# Pi-Switch-schematics.net
KiCad netlist of a schematic drawn in EAGLE
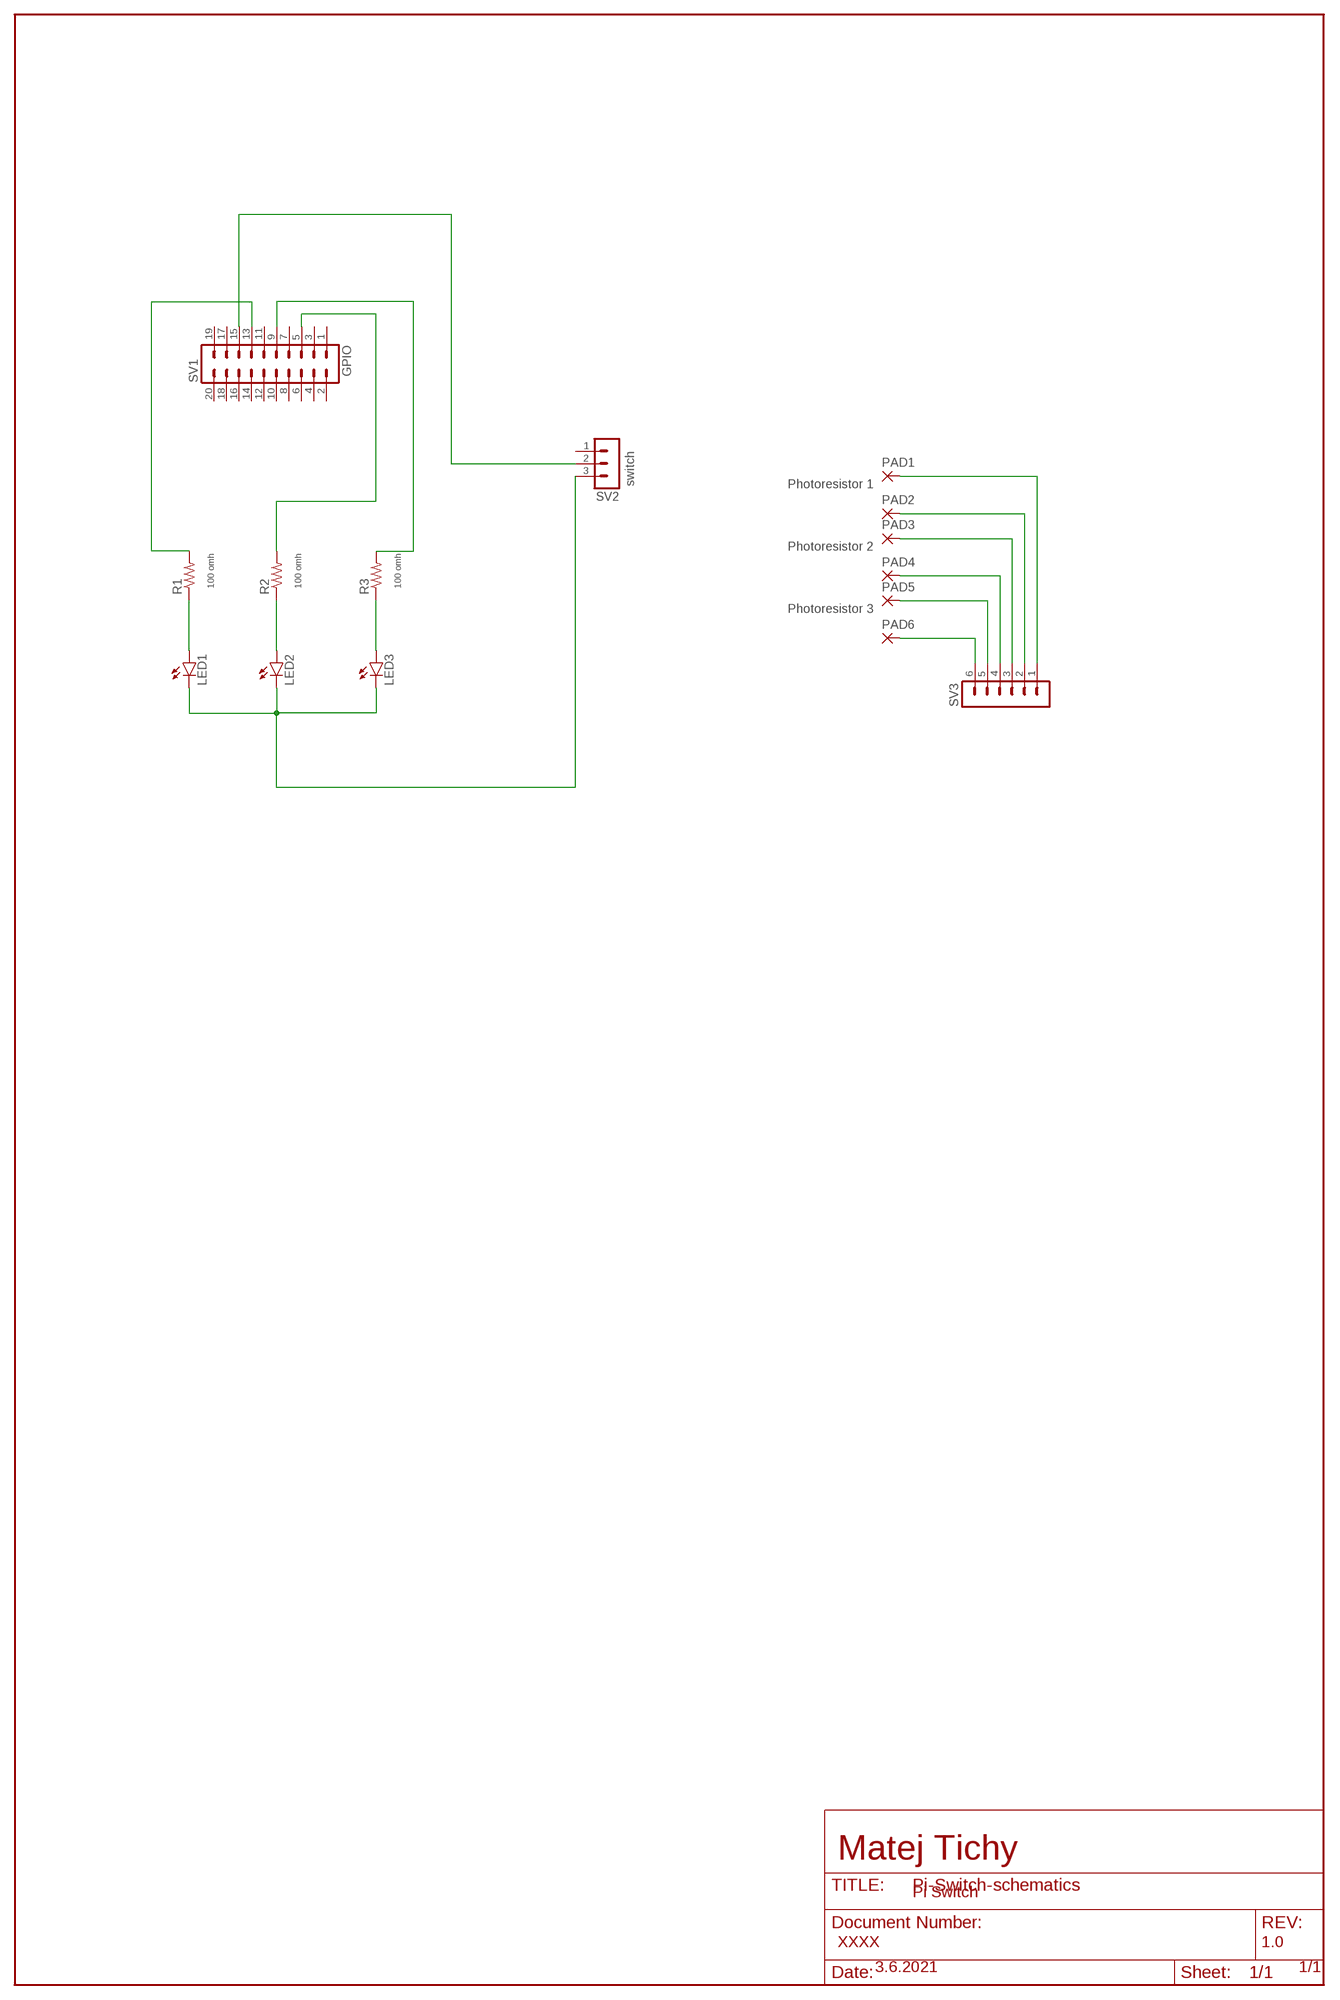
[diagram p0: schematic, sheet 1]

(export (version "E")
  (design (tool "Eeschema 10.0.6"))
  (components
    (comp (ref "LED1")
      (value "LED5MM")
      (footprint "eagle-import:LED5MM")
      (libsource (lib "eagle-import") (part "LED5MM"))
    )
    (comp (ref "LED2")
      (value "LED5MM")
      (footprint "eagle-import:LED5MM")
      (libsource (lib "eagle-import") (part "LED5MM"))
    )
    (comp (ref "LED3")
      (value "LED5MM")
      (footprint "eagle-import:LED5MM")
      (libsource (lib "eagle-import") (part "LED5MM"))
    )
    (comp (ref "PAD1")
      (value "1,6/0,8")
      (footprint "eagle-import:1,6_0,8")
      (libsource (lib "eagle-import") (part "1,6/0,8"))
    )
    (comp (ref "PAD2")
      (value "1,6/0,8")
      (footprint "eagle-import:1,6_0,8")
      (libsource (lib "eagle-import") (part "1,6/0,8"))
    )
    (comp (ref "PAD3")
      (value "1,6/0,8")
      (footprint "eagle-import:1,6_0,8")
      (libsource (lib "eagle-import") (part "1,6/0,8"))
    )
    (comp (ref "PAD4")
      (value "1,6/0,8")
      (footprint "eagle-import:1,6_0,8")
      (libsource (lib "eagle-import") (part "1,6/0,8"))
    )
    (comp (ref "PAD5")
      (value "1,6/0,8")
      (footprint "eagle-import:1,6_0,8")
      (libsource (lib "eagle-import") (part "1,6/0,8"))
    )
    (comp (ref "PAD6")
      (value "1,6/0,8")
      (footprint "eagle-import:1,6_0,8")
      (libsource (lib "eagle-import") (part "1,6/0,8"))
    )
    (comp (ref "R1")
      (value "R-US_0204/7")
      (footprint "eagle-import:0204_7")
      (libsource (lib "eagle-import") (part "R-US_0204/7"))
    )
    (comp (ref "R2")
      (value "R-US_0204/7")
      (footprint "eagle-import:0204_7")
      (libsource (lib "eagle-import") (part "R-US_0204/7"))
    )
    (comp (ref "R3")
      (value "R-US_0204/7")
      (footprint "eagle-import:0204_7")
      (libsource (lib "eagle-import") (part "R-US_0204/7"))
    )
    (comp (ref "SV1")
      (value "MA10-2")
      (footprint "eagle-import:MA10-2")
      (libsource (lib "eagle-import") (part "MA10-2"))
    )
    (comp (ref "SV2")
      (value "MA03-1")
      (footprint "eagle-import:MA03-1")
      (libsource (lib "eagle-import") (part "MA03-1"))
    )
    (comp (ref "SV3")
      (value "MA06-1")
      (footprint "eagle-import:MA06-1")
      (libsource (lib "eagle-import") (part "MA06-1"))
    )
  )
  (nets
    (net (code "1") (name "Net-(LED1-C)") (class "Default")
      (node (ref "LED1") (pin "K") (pinfunction "C_K") (pintype "passive"))
      (node (ref "LED2") (pin "K") (pinfunction "C_K") (pintype "passive"))
      (node (ref "LED3") (pin "K") (pinfunction "C_K") (pintype "passive"))
      (node (ref "SV2") (pin "3") (pinfunction "3_3") (pintype "passive"))
    )
    (net (code "2") (name "Net-(LED1-PadA)") (class "Default")
      (node (ref "LED1") (pin "A") (pinfunction "A_A") (pintype "passive"))
      (node (ref "R1") (pin "1") (pinfunction "1_1") (pintype "passive"))
    )
    (net (code "3") (name "Net-(LED2-PadA)") (class "Default")
      (node (ref "LED2") (pin "A") (pinfunction "A_A") (pintype "passive"))
      (node (ref "R2") (pin "1") (pinfunction "1_1") (pintype "passive"))
    )
    (net (code "4") (name "Net-(LED3-PadA)") (class "Default")
      (node (ref "LED3") (pin "A") (pinfunction "A_A") (pintype "passive"))
      (node (ref "R3") (pin "1") (pinfunction "1_1") (pintype "passive"))
    )
    (net (code "5") (name "Net-(PAD1-P)") (class "Default")
      (node (ref "PAD1") (pin "1") (pinfunction "P_1") (pintype "passive"))
      (node (ref "SV3") (pin "1") (pinfunction "1_1") (pintype "passive"))
    )
    (net (code "6") (name "Net-(PAD2-P)") (class "Default")
      (node (ref "PAD2") (pin "1") (pinfunction "P_1") (pintype "passive"))
      (node (ref "SV3") (pin "2") (pinfunction "2_2") (pintype "passive"))
    )
    (net (code "7") (name "Net-(PAD3-P)") (class "Default")
      (node (ref "PAD3") (pin "1") (pinfunction "P_1") (pintype "passive"))
      (node (ref "SV3") (pin "3") (pinfunction "3_3") (pintype "passive"))
    )
    (net (code "8") (name "Net-(PAD4-P)") (class "Default")
      (node (ref "PAD4") (pin "1") (pinfunction "P_1") (pintype "passive"))
      (node (ref "SV3") (pin "4") (pinfunction "4_4") (pintype "passive"))
    )
    (net (code "9") (name "Net-(PAD5-P)") (class "Default")
      (node (ref "PAD5") (pin "1") (pinfunction "P_1") (pintype "passive"))
      (node (ref "SV3") (pin "5") (pinfunction "5_5") (pintype "passive"))
    )
    (net (code "10") (name "Net-(PAD6-P)") (class "Default")
      (node (ref "PAD6") (pin "1") (pinfunction "P_1") (pintype "passive"))
      (node (ref "SV3") (pin "6") (pinfunction "6_6") (pintype "passive"))
    )
    (net (code "11") (name "Net-(R1-Pad2)") (class "Default")
      (node (ref "R1") (pin "2") (pinfunction "2_2") (pintype "passive"))
      (node (ref "SV1") (pin "13") (pinfunction "13_13") (pintype "passive"))
    )
    (net (code "12") (name "Net-(R2-Pad2)") (class "Default")
      (node (ref "R2") (pin "2") (pinfunction "2_2") (pintype "passive"))
      (node (ref "SV1") (pin "5") (pinfunction "5_5") (pintype "passive"))
    )
    (net (code "13") (name "Net-(R3-Pad2)") (class "Default")
      (node (ref "R3") (pin "2") (pinfunction "2_2") (pintype "passive"))
      (node (ref "SV1") (pin "9") (pinfunction "9_9") (pintype "passive"))
    )
    (net (code "14") (name "Net-(SV1-Pad15)") (class "Default")
      (node (ref "SV1") (pin "15") (pinfunction "15_15") (pintype "passive"))
      (node (ref "SV2") (pin "2") (pinfunction "2_2") (pintype "passive"))
    )
    (net (code "15") (name "unconnected-(SV1-Pad1)") (class "Default")
      (node (ref "SV1") (pin "1") (pinfunction "1_1") (pintype "passive"))
    )
    (net (code "16") (name "unconnected-(SV1-Pad2)") (class "Default")
      (node (ref "SV1") (pin "2") (pinfunction "2_2") (pintype "passive"))
    )
    (net (code "17") (name "unconnected-(SV1-Pad3)") (class "Default")
      (node (ref "SV1") (pin "3") (pinfunction "3_3") (pintype "passive"))
    )
    (net (code "18") (name "unconnected-(SV1-Pad4)") (class "Default")
      (node (ref "SV1") (pin "4") (pinfunction "4_4") (pintype "passive"))
    )
    (net (code "19") (name "unconnected-(SV1-Pad6)") (class "Default")
      (node (ref "SV1") (pin "6") (pinfunction "6_6") (pintype "passive"))
    )
    (net (code "20") (name "unconnected-(SV1-Pad7)") (class "Default")
      (node (ref "SV1") (pin "7") (pinfunction "7_7") (pintype "passive"))
    )
    (net (code "21") (name "unconnected-(SV1-Pad8)") (class "Default")
      (node (ref "SV1") (pin "8") (pinfunction "8_8") (pintype "passive"))
    )
    (net (code "22") (name "unconnected-(SV1-Pad10)") (class "Default")
      (node (ref "SV1") (pin "10") (pinfunction "10_10") (pintype "passive"))
    )
    (net (code "23") (name "unconnected-(SV1-Pad11)") (class "Default")
      (node (ref "SV1") (pin "11") (pinfunction "11_11") (pintype "passive"))
    )
    (net (code "24") (name "unconnected-(SV1-Pad12)") (class "Default")
      (node (ref "SV1") (pin "12") (pinfunction "12_12") (pintype "passive"))
    )
    (net (code "25") (name "unconnected-(SV1-Pad14)") (class "Default")
      (node (ref "SV1") (pin "14") (pinfunction "14_14") (pintype "passive"))
    )
    (net (code "26") (name "unconnected-(SV1-Pad16)") (class "Default")
      (node (ref "SV1") (pin "16") (pinfunction "16_16") (pintype "passive"))
    )
    (net (code "27") (name "unconnected-(SV1-Pad17)") (class "Default")
      (node (ref "SV1") (pin "17") (pinfunction "17_17") (pintype "passive"))
    )
    (net (code "28") (name "unconnected-(SV1-Pad18)") (class "Default")
      (node (ref "SV1") (pin "18") (pinfunction "18_18") (pintype "passive"))
    )
    (net (code "29") (name "unconnected-(SV1-Pad19)") (class "Default")
      (node (ref "SV1") (pin "19") (pinfunction "19_19") (pintype "passive"))
    )
    (net (code "30") (name "unconnected-(SV1-Pad20)") (class "Default")
      (node (ref "SV1") (pin "20") (pinfunction "20_20") (pintype "passive"))
    )
    (net (code "31") (name "unconnected-(SV2-Pad1)") (class "Default")
      (node (ref "SV2") (pin "1") (pinfunction "1_1") (pintype "passive"))
    )
  )
)
